# blinkm2neo_5Jul2020_isp.net
KiCad netlist of a schematic drawn in EAGLE
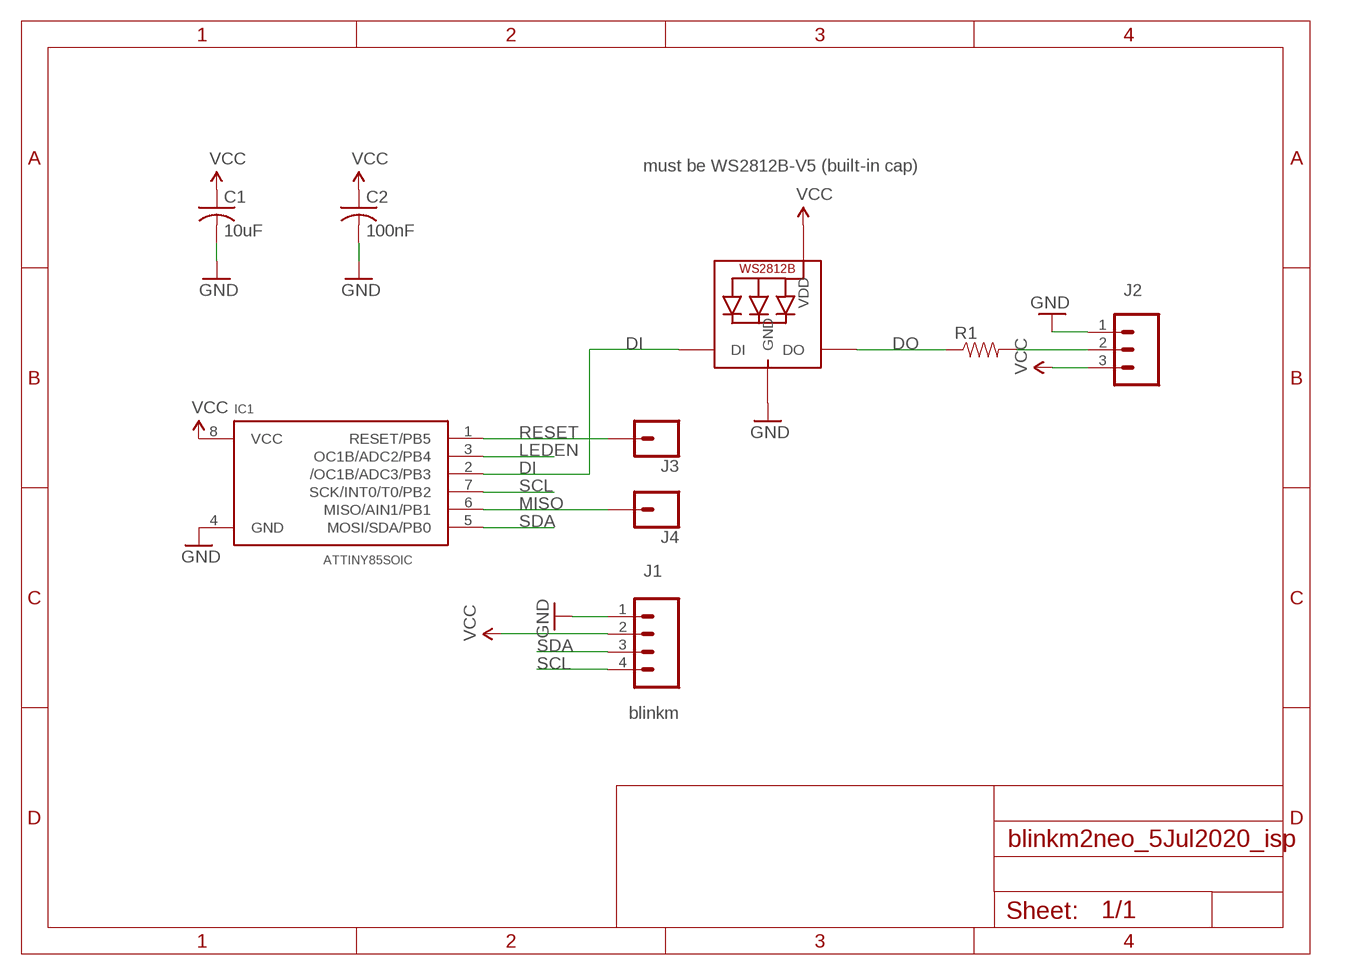
[diagram p0: schematic, sheet 1]

(export (version "E")
  (design (tool "Eeschema 10.0.6"))
  (components
    (comp (ref "C1")
      (value "10uF")
      (footprint "eagle-import:C0402")
      (libsource (lib "eagle-import") (part "C-USC0402"))
    )
    (comp (ref "C2")
      (value "100nF")
      (footprint "eagle-import:C0402")
      (libsource (lib "eagle-import") (part "C-USC0402"))
    )
    (comp (ref "IC1")
      (value "ATTINY85SOIC")
      (footprint "eagle-import:SO08-EIAJ")
      (libsource (lib "eagle-import") (part "ATTINY45SOIC"))
    )
    (comp (ref "J1")
      (value "blinkm")
      (footprint "eagle-import:1X04")
      (libsource (lib "eagle-import") (part "CONN_04"))
    )
    (comp (ref "J2")
      (value "CONN_03")
      (footprint "eagle-import:1X03")
      (libsource (lib "eagle-import") (part "CONN_03"))
    )
    (comp (ref "J3")
      (value "CONN_01PTH_NO_SILK_YES_STOP")
      (footprint "eagle-import:1X01_NO_SILK")
      (libsource (lib "eagle-import") (part "CONN_01PTH_NO_SILK_YES_STOP"))
    )
    (comp (ref "J4")
      (value "CONN_01PTH_NO_SILK_YES_STOP")
      (footprint "eagle-import:1X01_NO_SILK")
      (libsource (lib "eagle-import") (part "CONN_01PTH_NO_SILK_YES_STOP"))
    )
    (comp (ref "LED1")
      (value "WS2812B-V5")
      (footprint "eagle-import:WS2812B")
      (libsource (lib "eagle-import") (part "WS2812B5050"))
    )
    (comp (ref "R1")
      (value "RESISTOR0402")
      (footprint "eagle-import:0402")
      (libsource (lib "eagle-import") (part "RESISTOR0402"))
    )
  )
  (nets
    (net (code "1") (name "/DI") (class "Default")
      (node (ref "IC1") (pin "2") (pinfunction "/OC1B/ADC3/PB3_2") (pintype "bidirectional"))
      (node (ref "LED1") (pin "4-DIN") (pinfunction "DI_4-DIN") (pintype "input"))
    )
    (net (code "2") (name "/DO") (class "Default")
      (node (ref "LED1") (pin "2-DOUT") (pinfunction "DO_2-DOUT") (pintype "output"))
      (node (ref "R1") (pin "1") (pinfunction "1_1") (pintype "passive"))
    )
    (net (code "3") (name "/LEDEN") (class "Default")
      (node (ref "IC1") (pin "3") (pinfunction "OC1B/ADC2/PB4_3") (pintype "bidirectional"))
    )
    (net (code "4") (name "/MISO") (class "Default")
      (node (ref "IC1") (pin "6") (pinfunction "MISO/AIN1/PB1_6") (pintype "bidirectional"))
      (node (ref "J4") (pin "1") (pinfunction "1_1") (pintype "passive"))
    )
    (net (code "5") (name "/RESET") (class "Default")
      (node (ref "IC1") (pin "1") (pinfunction "RESET/PB5_1") (pintype "bidirectional"))
      (node (ref "J3") (pin "1") (pinfunction "1_1") (pintype "passive"))
    )
    (net (code "6") (name "/SCL") (class "Default")
      (node (ref "IC1") (pin "7") (pinfunction "SCK/INT0/T0/PB2_7") (pintype "bidirectional"))
      (node (ref "J1") (pin "4") (pinfunction "4_4") (pintype "passive"))
    )
    (net (code "7") (name "/SDA") (class "Default")
      (node (ref "IC1") (pin "5") (pinfunction "MOSI/SDA/PB0_5") (pintype "bidirectional"))
      (node (ref "J1") (pin "3") (pinfunction "3_3") (pintype "passive"))
    )
    (net (code "8") (name "GND") (class "Default")
      (node (ref "C1") (pin "2") (pinfunction "2_2") (pintype "passive"))
      (node (ref "C2") (pin "2") (pinfunction "2_2") (pintype "passive"))
      (node (ref "IC1") (pin "4") (pinfunction "GND_4") (pintype "bidirectional"))
      (node (ref "J1") (pin "1") (pinfunction "1_1") (pintype "passive"))
      (node (ref "J2") (pin "1") (pinfunction "1_1") (pintype "passive"))
      (node (ref "LED1") (pin "3-GND") (pinfunction "GND_3-GND") (pintype "power_in"))
    )
    (net (code "9") (name "Net-(J2-Pad2)") (class "Default")
      (node (ref "J2") (pin "2") (pinfunction "2_2") (pintype "passive"))
      (node (ref "R1") (pin "2") (pinfunction "2_2") (pintype "passive"))
    )
    (net (code "10") (name "VCC") (class "Default")
      (node (ref "C1") (pin "1") (pinfunction "1_1") (pintype "passive"))
      (node (ref "C2") (pin "1") (pinfunction "1_1") (pintype "passive"))
      (node (ref "IC1") (pin "8") (pinfunction "VCC_8") (pintype "bidirectional"))
      (node (ref "J1") (pin "2") (pinfunction "2_2") (pintype "passive"))
      (node (ref "J2") (pin "3") (pinfunction "3_3") (pintype "passive"))
      (node (ref "LED1") (pin "1-VDD") (pinfunction "VDD_1-VDD") (pintype "power_in"))
    )
  )
)
